# SERIAL_IF.net
KiCad netlist of a schematic drawn in Altium Designer
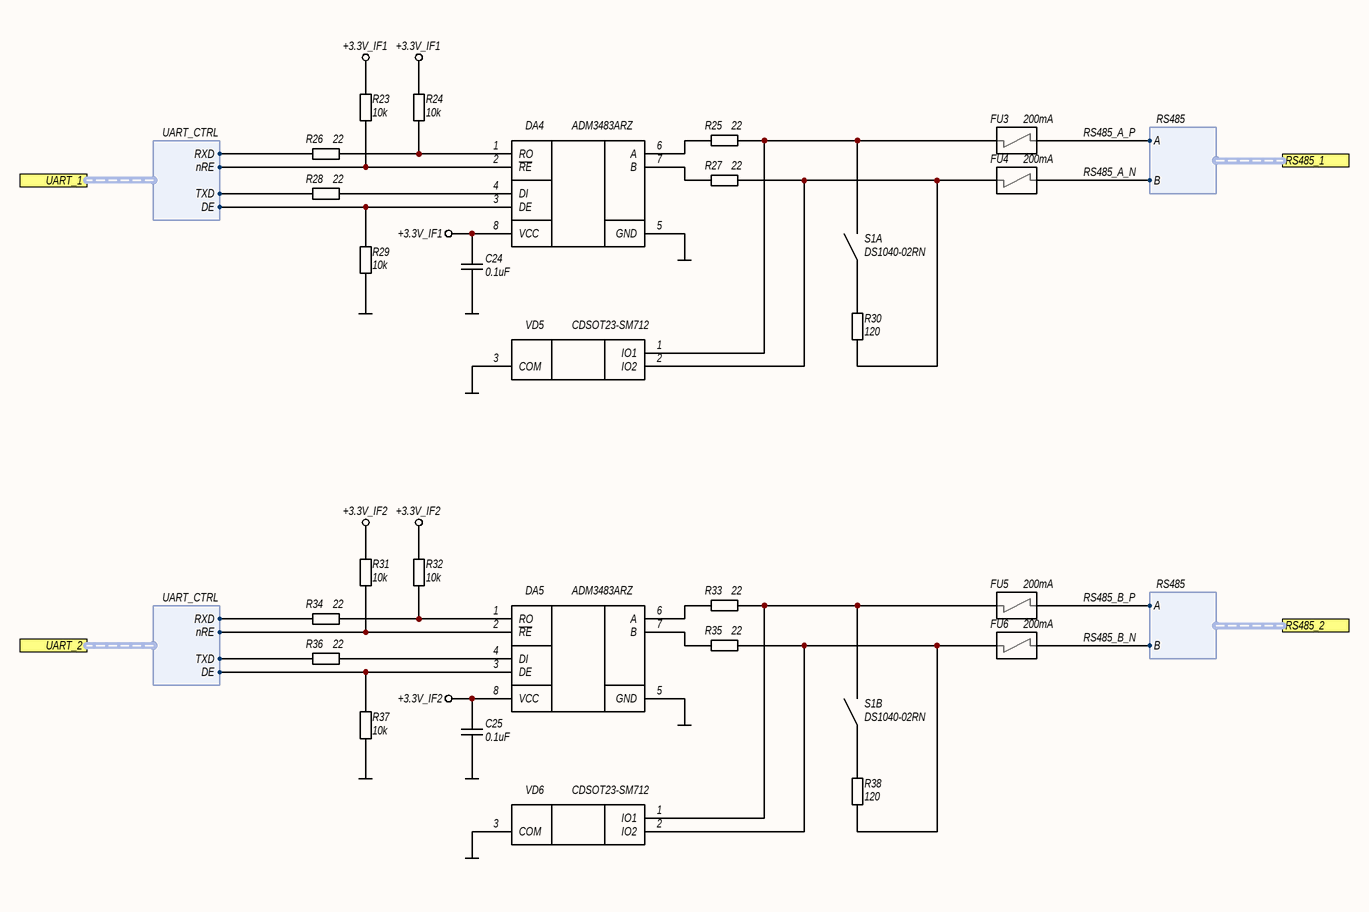
[diagram p0: SERIAL_IF.SchDoc]

(export (version "E")
  (design (tool "Eeschema 10.0.6"))
  (components
    (comp (ref "C24")
      (value "0.1uF")
      (footprint "C0603N")
      (description "Конденсатор")
      (libsource (lib "Components Library") (part "CAP_FIXED"))
    )
    (comp (ref "C25")
      (value "0.1uF")
      (footprint "C0603N")
      (description "Конденсатор")
      (libsource (lib "Components Library") (part "CAP_FIXED"))
    )
    (comp (ref "DA4")
      (value "ADM3483ARZ")
      (footprint "SOIC8")
      (description "Микросхема приемопередатчика RS-485")
      (libsource (lib "Components Library") (part "ADM3483_5"))
    )
    (comp (ref "DA5")
      (value "ADM3483ARZ")
      (footprint "SOIC8")
      (description "Микросхема приемопередатчика RS-485")
      (libsource (lib "Components Library") (part "ADM3483_5"))
    )
    (comp (ref "FU3")
      (value "200mA")
      (footprint "TBU-CA")
      (description "Полупроводниковый предохранитель")
      (libsource (lib "Components Library") (part "FUSE_TBU"))
    )
    (comp (ref "FU4")
      (value "200mA")
      (footprint "TBU-CA")
      (description "Полупроводниковый предохранитель")
      (libsource (lib "Components Library") (part "FUSE_TBU"))
    )
    (comp (ref "FU5")
      (value "200mA")
      (footprint "TBU-CA")
      (description "Полупроводниковый предохранитель")
      (libsource (lib "Components Library") (part "FUSE_TBU"))
    )
    (comp (ref "FU6")
      (value "200mA")
      (footprint "TBU-CA")
      (description "Полупроводниковый предохранитель")
      (libsource (lib "Components Library") (part "FUSE_TBU"))
    )
    (comp (ref "R23")
      (value "10k")
      (footprint "R0603N")
      (description "Резистор")
      (libsource (lib "Components Library") (part "RES_FIXED"))
    )
    (comp (ref "R24")
      (value "10k")
      (footprint "R0603N")
      (description "Резистор")
      (libsource (lib "Components Library") (part "RES_FIXED"))
    )
    (comp (ref "R25")
      (value "22")
      (footprint "R0805N")
      (description "Резистор")
      (libsource (lib "") (part "RES_FIXED_1"))
    )
    (comp (ref "R26")
      (value "22")
      (footprint "R0603N")
      (description "Резистор")
      (libsource (lib "") (part "RES_FIXED_1"))
    )
    (comp (ref "R27")
      (value "22")
      (footprint "R0805N")
      (description "Резистор")
      (libsource (lib "") (part "RES_FIXED_1"))
    )
    (comp (ref "R28")
      (value "22")
      (footprint "R0603N")
      (description "Резистор")
      (libsource (lib "") (part "RES_FIXED_1"))
    )
    (comp (ref "R29")
      (value "10k")
      (footprint "R0603N")
      (description "Резистор")
      (libsource (lib "Components Library") (part "RES_FIXED"))
    )
    (comp (ref "R30")
      (value "120")
      (footprint "R1206N")
      (description "Резистор")
      (libsource (lib "Components Library") (part "RES_FIXED"))
    )
    (comp (ref "R31")
      (value "10k")
      (footprint "R0603N")
      (description "Резистор")
      (libsource (lib "Components Library") (part "RES_FIXED"))
    )
    (comp (ref "R32")
      (value "10k")
      (footprint "R0603N")
      (description "Резистор")
      (libsource (lib "Components Library") (part "RES_FIXED"))
    )
    (comp (ref "R33")
      (value "22")
      (footprint "R0805N")
      (description "Резистор")
      (libsource (lib "") (part "RES_FIXED_1"))
    )
    (comp (ref "R34")
      (value "22")
      (footprint "R0603N")
      (description "Резистор")
      (libsource (lib "") (part "RES_FIXED_1"))
    )
    (comp (ref "R35")
      (value "22")
      (footprint "R0805N")
      (description "Резистор")
      (libsource (lib "") (part "RES_FIXED_1"))
    )
    (comp (ref "R36")
      (value "22")
      (footprint "R0603N")
      (description "Резистор")
      (libsource (lib "") (part "RES_FIXED_1"))
    )
    (comp (ref "R37")
      (value "10k")
      (footprint "R0603N")
      (description "Резистор")
      (libsource (lib "Components Library") (part "RES_FIXED"))
    )
    (comp (ref "R38")
      (value "120")
      (footprint "R1206N")
      (description "Резистор")
      (libsource (lib "Components Library") (part "RES_FIXED"))
    )
    (comp (ref "S1")
      (value "DS1040-02RN")
      (footprint "DIP_SWITCH_02P_STR_RA_TH")
      (description "Выключатель, DPST-NO")
      (libsource (lib "Components Library") (part "SWITCH_DPST-NO"))
    )
    (comp (ref "VD5")
      (value "CDSOT23-SM712")
      (footprint "SOT23")
      (description "Сборка TVS диодов")
      (libsource (lib "Components Library") (part "CDSOT23-SM712"))
    )
    (comp (ref "VD6")
      (value "CDSOT23-SM712")
      (footprint "SOT23")
      (description "Сборка TVS диодов")
      (libsource (lib "Components Library") (part "CDSOT23-SM712"))
    )
  )
  (nets
    (net (code "3") (name "+3.3V_IF1") (class "Default")
      (node (ref "C24") (pin "1") (pinfunction "1_1") (pintype "passive"))
      (node (ref "DA4") (pin "8") (pinfunction "VCC_8") (pintype "power_in"))
      (node (ref "R23") (pin "1") (pinfunction "1_1") (pintype "passive"))
      (node (ref "R24") (pin "1") (pinfunction "1_1") (pintype "passive"))
    )
    (net (code "4") (name "+3.3V_IF2") (class "Default")
      (node (ref "C25") (pin "1") (pinfunction "1_1") (pintype "passive"))
      (node (ref "DA5") (pin "8") (pinfunction "VCC_8") (pintype "power_in"))
      (node (ref "R31") (pin "1") (pinfunction "1_1") (pintype "passive"))
      (node (ref "R32") (pin "1") (pinfunction "1_1") (pintype "passive"))
    )
    (net (code "5") (name "/RS485_A_N") (class "Default")
      (node (ref "FU4") (pin "3") (pinfunction "IN/OUT_3") (pintype "passive"))
    )
    (net (code "6") (name "/RS485_A_P") (class "Default")
      (node (ref "FU3") (pin "3") (pinfunction "IN/OUT_3") (pintype "passive"))
    )
    (net (code "7") (name "/RS485_B_N") (class "Default")
      (node (ref "FU6") (pin "3") (pinfunction "IN/OUT_3") (pintype "passive"))
    )
    (net (code "8") (name "/RS485_B_P") (class "Default")
      (node (ref "FU5") (pin "3") (pinfunction "IN/OUT_3") (pintype "passive"))
    )
    (net (code "11") (name "GND") (class "Default")
      (node (ref "C24") (pin "2") (pinfunction "2_2") (pintype "passive"))
      (node (ref "C25") (pin "2") (pinfunction "2_2") (pintype "passive"))
      (node (ref "DA4") (pin "5") (pinfunction "GND_5") (pintype "power_in"))
      (node (ref "DA5") (pin "5") (pinfunction "GND_5") (pintype "power_in"))
      (node (ref "R29") (pin "2") (pinfunction "2_2") (pintype "passive"))
      (node (ref "R37") (pin "2") (pinfunction "2_2") (pintype "passive"))
      (node (ref "VD5") (pin "3") (pinfunction "COM_3") (pintype "power_in"))
      (node (ref "VD6") (pin "3") (pinfunction "COM_3") (pintype "power_in"))
    )
    (net (code "12") (name "Net-(DA4-A)") (class "Default")
      (node (ref "DA4") (pin "6") (pinfunction "A_6") (pintype "power_in"))
      (node (ref "R25") (pin "2") (pinfunction "2_2") (pintype "passive"))
    )
    (net (code "13") (name "Net-(DA4-B)") (class "Default")
      (node (ref "DA4") (pin "7") (pinfunction "B_7") (pintype "power_in"))
      (node (ref "R27") (pin "2") (pinfunction "2_2") (pintype "passive"))
    )
    (net (code "14") (name "Net-(DA4-DE)") (class "Default")
      (node (ref "DA4") (pin "3") (pinfunction "DE_3") (pintype "power_in"))
      (node (ref "R29") (pin "1") (pinfunction "1_1") (pintype "passive"))
    )
    (net (code "15") (name "Net-(DA4-DI)") (class "Default")
      (node (ref "DA4") (pin "4") (pinfunction "DI_4") (pintype "power_in"))
      (node (ref "R28") (pin "1") (pinfunction "1_1") (pintype "passive"))
    )
    (net (code "16") (name "Net-(DA4-RO)") (class "Default")
      (node (ref "DA4") (pin "1") (pinfunction "RO_1") (pintype "power_in"))
      (node (ref "R24") (pin "2") (pinfunction "2_2") (pintype "passive"))
      (node (ref "R26") (pin "1") (pinfunction "1_1") (pintype "passive"))
    )
    (net (code "17") (name "Net-(DA4-~{RE})") (class "Default")
      (node (ref "DA4") (pin "2") (pinfunction "~{RE}_2") (pintype "power_in"))
      (node (ref "R23") (pin "2") (pinfunction "2_2") (pintype "passive"))
    )
    (net (code "18") (name "Net-(DA5-A)") (class "Default")
      (node (ref "DA5") (pin "6") (pinfunction "A_6") (pintype "power_in"))
      (node (ref "R33") (pin "2") (pinfunction "2_2") (pintype "passive"))
    )
    (net (code "19") (name "Net-(DA5-B)") (class "Default")
      (node (ref "DA5") (pin "7") (pinfunction "B_7") (pintype "power_in"))
      (node (ref "R35") (pin "2") (pinfunction "2_2") (pintype "passive"))
    )
    (net (code "20") (name "Net-(DA5-DE)") (class "Default")
      (node (ref "DA5") (pin "3") (pinfunction "DE_3") (pintype "power_in"))
      (node (ref "R37") (pin "1") (pinfunction "1_1") (pintype "passive"))
    )
    (net (code "21") (name "Net-(DA5-DI)") (class "Default")
      (node (ref "DA5") (pin "4") (pinfunction "DI_4") (pintype "power_in"))
      (node (ref "R36") (pin "1") (pinfunction "1_1") (pintype "passive"))
    )
    (net (code "22") (name "Net-(DA5-RO)") (class "Default")
      (node (ref "DA5") (pin "1") (pinfunction "RO_1") (pintype "power_in"))
      (node (ref "R32") (pin "2") (pinfunction "2_2") (pintype "passive"))
      (node (ref "R34") (pin "1") (pinfunction "1_1") (pintype "passive"))
    )
    (net (code "23") (name "Net-(DA5-~{RE})") (class "Default")
      (node (ref "DA5") (pin "2") (pinfunction "~{RE}_2") (pintype "power_in"))
      (node (ref "R31") (pin "2") (pinfunction "2_2") (pintype "passive"))
    )
    (net (code "24") (name "Net-(S1A-11)") (class "Default")
      (node (ref "R30") (pin "1") (pinfunction "1_1") (pintype "passive"))
      (node (ref "S1") (pin "1") (pinfunction "11_1") (pintype "passive"))
    )
    (net (code "25") (name "Net-(S1A-12)") (class "Default")
      (node (ref "FU3") (pin "1") (pinfunction "IN/OUT_1") (pintype "passive"))
      (node (ref "R25") (pin "1") (pinfunction "1_1") (pintype "passive"))
      (node (ref "S1") (pin "4") (pinfunction "12_4") (pintype "passive"))
      (node (ref "VD5") (pin "1") (pinfunction "IO1_1") (pintype "power_in"))
    )
    (net (code "26") (name "Net-(S1B-21)") (class "Default")
      (node (ref "R38") (pin "1") (pinfunction "1_1") (pintype "passive"))
      (node (ref "S1") (pin "2") (pinfunction "21_2") (pintype "passive"))
    )
    (net (code "27") (name "Net-(S1B-22)") (class "Default")
      (node (ref "FU5") (pin "1") (pinfunction "IN/OUT_1") (pintype "passive"))
      (node (ref "R33") (pin "1") (pinfunction "1_1") (pintype "passive"))
      (node (ref "S1") (pin "3") (pinfunction "22_3") (pintype "passive"))
      (node (ref "VD6") (pin "1") (pinfunction "IO1_1") (pintype "power_in"))
    )
    (net (code "28") (name "Net-(VD5-IO2)") (class "Default")
      (node (ref "FU4") (pin "1") (pinfunction "IN/OUT_1") (pintype "passive"))
      (node (ref "R27") (pin "1") (pinfunction "1_1") (pintype "passive"))
      (node (ref "R30") (pin "2") (pinfunction "2_2") (pintype "passive"))
      (node (ref "VD5") (pin "2") (pinfunction "IO2_2") (pintype "power_in"))
    )
    (net (code "29") (name "Net-(VD6-IO2)") (class "Default")
      (node (ref "FU6") (pin "1") (pinfunction "IN/OUT_1") (pintype "passive"))
      (node (ref "R35") (pin "1") (pinfunction "1_1") (pintype "passive"))
      (node (ref "R38") (pin "2") (pinfunction "2_2") (pintype "passive"))
      (node (ref "VD6") (pin "2") (pinfunction "IO2_2") (pintype "power_in"))
    )
    (net (code "30") (name "unconnected-(R26-Pad2)") (class "Default")
      (node (ref "R26") (pin "2") (pinfunction "2_2") (pintype "passive"))
    )
    (net (code "31") (name "unconnected-(R28-Pad2)") (class "Default")
      (node (ref "R28") (pin "2") (pinfunction "2_2") (pintype "passive"))
    )
    (net (code "32") (name "unconnected-(R34-Pad2)") (class "Default")
      (node (ref "R34") (pin "2") (pinfunction "2_2") (pintype "passive"))
    )
    (net (code "33") (name "unconnected-(R36-Pad2)") (class "Default")
      (node (ref "R36") (pin "2") (pinfunction "2_2") (pintype "passive"))
    )
  )
)
